# 07_Power_socket_roller_feed.net
KiCad netlist of a schematic drawn in Altium Designer
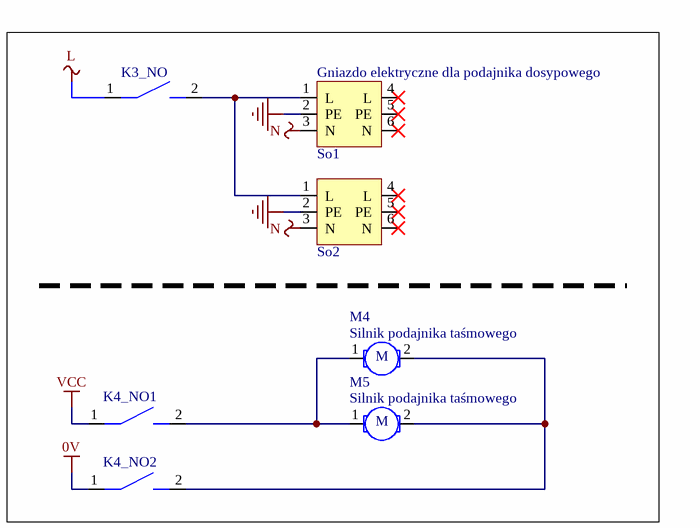
[diagram p0: [07] Power socket, roller feed.SchDoc]

(export (version "E")
  (design (tool "Eeschema 10.0.6"))
  (components
    (comp (ref "K3_NO") (value "NO") (libsource (lib "Schlib1") (part "NO")))
    (comp (ref "K4_NO1") (value "NO") (libsource (lib "Schlib1") (part "NO")))
    (comp (ref "K4_NO2") (value "NO") (libsource (lib "Schlib1") (part "NO")))
    (comp (ref "M4") (value "Silnik podajnika taśmowego") (libsource (lib "Schlib1") (part "DC motor")))
    (comp (ref "M5") (value "Silnik podajnika taśmowego") (libsource (lib "Schlib1") (part "DC motor")))
    (comp (ref "So1")
      (value "Gniazdo elektryczne dla podajnika dosypowego")
      (libsource (lib "Schlib1") (part "Power socket"))
    )
    (comp (ref "So2") (value "Power socket") (libsource (lib "Schlib1") (part "Power socket")))
  )
  (nets
    (net (code "1") (name "0V") (class "Default")
      (node (ref "K4_NO2") (pin "1") (pinfunction "*_1") (pintype "passive"))
    )
    (net (code "2") (name "<NO NET>") (class "Default")
      (node (ref "So1") (pin "2") (pinfunction "PE_2") (pintype "passive"))
      (node (ref "So2") (pin "2") (pinfunction "PE_2") (pintype "passive"))
    )
    (net (code "4") (name "N") (class "Default")
      (node (ref "So1") (pin "3") (pinfunction "N_3") (pintype "passive"))
      (node (ref "So2") (pin "3") (pinfunction "N_3") (pintype "passive"))
    )
    (net (code "5") (name "Net-(K3_NO-*-Pad2)") (class "Default")
      (node (ref "K3_NO") (pin "2") (pinfunction "*_2") (pintype "passive"))
      (node (ref "So1") (pin "1") (pinfunction "L_1") (pintype "passive"))
      (node (ref "So2") (pin "1") (pinfunction "L_1") (pintype "passive"))
    )
    (net (code "6") (name "Net-(M4-15)") (class "Default")
      (node (ref "K4_NO2") (pin "2") (pinfunction "*_2") (pintype "passive"))
      (node (ref "M4") (pin "2") (pinfunction "15_2") (pintype "passive"))
      (node (ref "M5") (pin "2") (pinfunction "15_2") (pintype "passive"))
    )
    (net (code "7") (name "Net-(M4-16)") (class "Default")
      (node (ref "K4_NO1") (pin "2") (pinfunction "*_2") (pintype "passive"))
      (node (ref "M4") (pin "1") (pinfunction "16_1") (pintype "passive"))
      (node (ref "M5") (pin "1") (pinfunction "16_1") (pintype "passive"))
    )
    (net (code "8") (name "VCC") (class "Default")
      (node (ref "K4_NO1") (pin "1") (pinfunction "*_1") (pintype "passive"))
    )
    (net (code "9") (name "unconnected-(K3_NO-*-Pad1)") (class "Default")
      (node (ref "K3_NO") (pin "1") (pinfunction "*_1") (pintype "passive"))
    )
    (net (code "10") (name "unconnected-(So1-L-Pad4)") (class "Default")
      (node (ref "So1") (pin "4") (pinfunction "L_4") (pintype "passive+no_connect"))
    )
    (net (code "11") (name "unconnected-(So1-N-Pad6)") (class "Default")
      (node (ref "So1") (pin "6") (pinfunction "N_6") (pintype "passive+no_connect"))
    )
    (net (code "12") (name "unconnected-(So1-PE-Pad5)") (class "Default")
      (node (ref "So1") (pin "5") (pinfunction "PE_5") (pintype "passive+no_connect"))
    )
    (net (code "13") (name "unconnected-(So2-L-Pad4)") (class "Default")
      (node (ref "So2") (pin "4") (pinfunction "L_4") (pintype "passive+no_connect"))
    )
    (net (code "14") (name "unconnected-(So2-N-Pad6)") (class "Default")
      (node (ref "So2") (pin "6") (pinfunction "N_6") (pintype "passive+no_connect"))
    )
    (net (code "15") (name "unconnected-(So2-PE-Pad5)") (class "Default")
      (node (ref "So2") (pin "5") (pinfunction "PE_5") (pintype "passive+no_connect"))
    )
  )
)
